# Fubarino_SD_v14.net
KiCad netlist of a schematic drawn in EAGLE
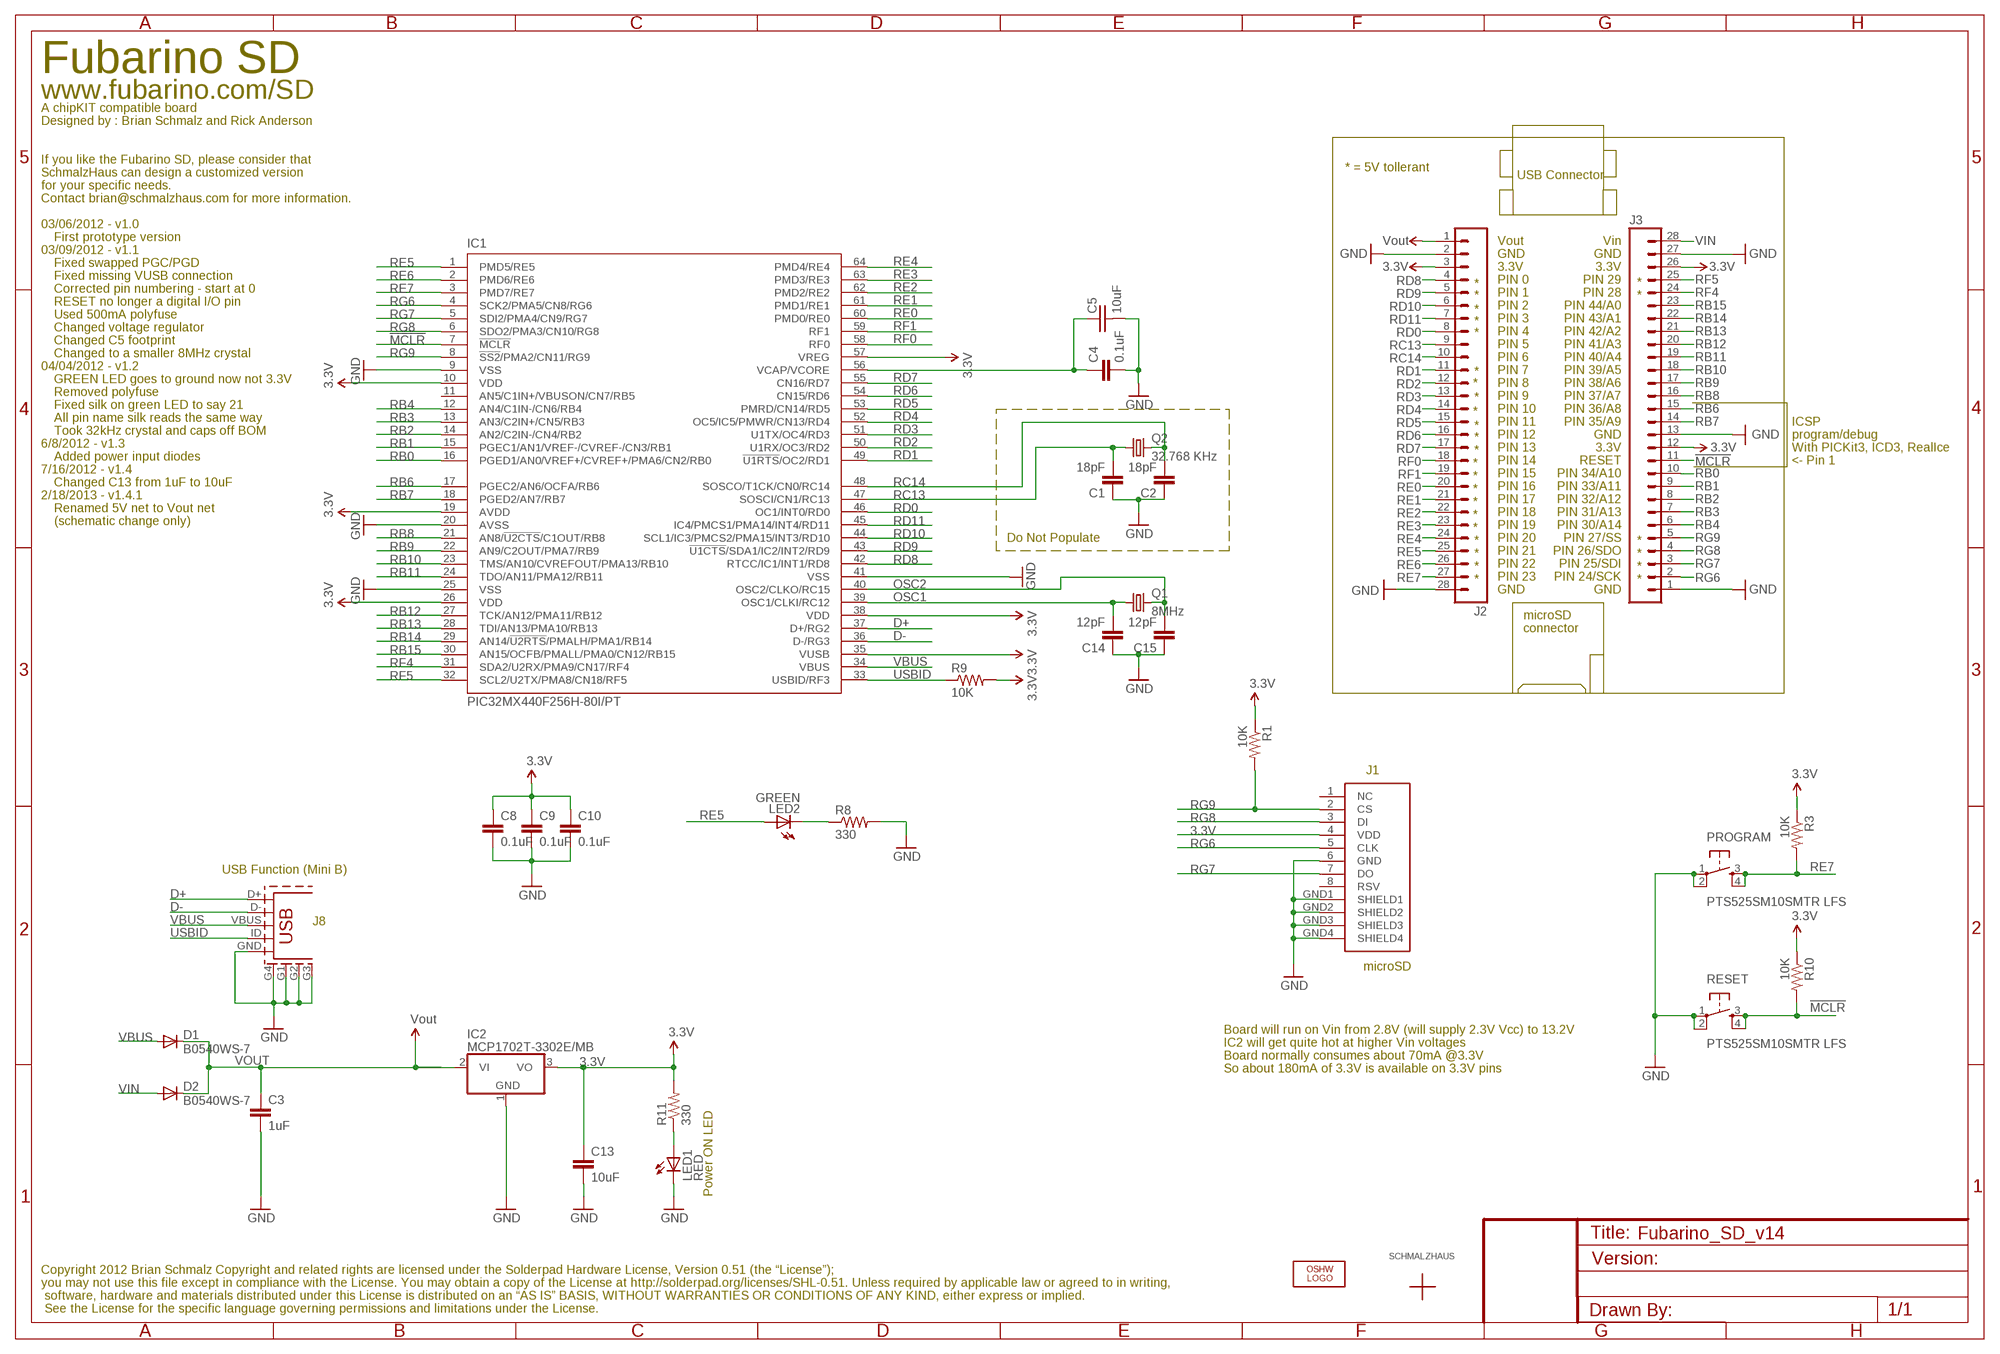
[diagram p0: schematic, sheet 1]

(export (version "E")
  (design (tool "Eeschema 10.0.6"))
  (components
    (comp (ref "C1")
      (value "18pF")
      (footprint "eagle-import:0603-CAP")
      (libsource (lib "eagle-import") (part "CAP0603-CAP"))
    )
    (comp (ref "C2")
      (value "18pF")
      (footprint "eagle-import:0603-CAP")
      (libsource (lib "eagle-import") (part "CAP0603-CAP"))
    )
    (comp (ref "C3")
      (value "1uF")
      (footprint "eagle-import:0603-CAP")
      (libsource (lib "eagle-import") (part "CAP0603-CAP"))
    )
    (comp (ref "C4")
      (value "0.1uF")
      (footprint "eagle-import:0603-CAP")
      (libsource (lib "eagle-import") (part "CAP0603-CAP"))
    )
    (comp (ref "C5")
      (value "10uF")
      (footprint "eagle-import:CAP_0805")
      (libsource (lib "eagle-import") (part "CAP0805"))
    )
    (comp (ref "C8")
      (value "0.1uF")
      (footprint "eagle-import:0603-CAP")
      (libsource (lib "eagle-import") (part "CAP0603-CAP"))
    )
    (comp (ref "C9")
      (value "0.1uF")
      (footprint "eagle-import:0603-CAP")
      (libsource (lib "eagle-import") (part "CAP0603-CAP"))
    )
    (comp (ref "C10")
      (value "0.1uF")
      (footprint "eagle-import:0603")
      (libsource (lib "eagle-import") (part "CAP0603"))
    )
    (comp (ref "C13")
      (value "10uF")
      (footprint "eagle-import:0805")
      (libsource (lib "eagle-import") (part "SparkFun02-20-08_CAP0805"))
    )
    (comp (ref "C14")
      (value "12pF")
      (footprint "eagle-import:0603-CAP")
      (libsource (lib "eagle-import") (part "CAP0603-CAP"))
    )
    (comp (ref "C15")
      (value "12pF")
      (footprint "eagle-import:0603-CAP")
      (libsource (lib "eagle-import") (part "CAP0603-CAP"))
    )
    (comp (ref "D1")
      (value "B0540WS-7")
      (footprint "eagle-import:SOD-323")
      (libsource (lib "eagle-import") (part "DIODESOD"))
    )
    (comp (ref "D2")
      (value "B0540WS-7")
      (footprint "eagle-import:SOD-323")
      (libsource (lib "eagle-import") (part "DIODESOD"))
    )
    (comp (ref "IC1")
      (value "PIC32MX440F256H-80I/PT")
      (footprint "eagle-import:TQFP64-10X10")
      (libsource (lib "eagle-import") (part "PIC32MX440F256H"))
    )
    (comp (ref "IC2")
      (value "MCP1702T-3302E/MB")
      (footprint "eagle-import:SOT89")
      (libsource (lib "eagle-import") (part "MCP1703MB33"))
    )
    (comp (ref "J1")
      (value "MICRO_SD_CARD_SOCKET")
      (footprint "eagle-import:SD-MMC_SOCKET-PP")
      (libsource (lib "eagle-import") (part "MICRO_SD_CARD_SOCKET"))
    )
    (comp (ref "J2")
      (value "M28USEPIN1")
      (footprint "eagle-import:1X28")
      (libsource (lib "eagle-import") (part "M28USEPIN1"))
    )
    (comp (ref "J3")
      (value "M28NOPIN1")
      (footprint "eagle-import:1X28_NO_PIN_1")
      (libsource (lib "eagle-import") (part "M28NOPIN1"))
    )
    (comp (ref "J8")
      (value "UX60A-MB-5ST")
      (footprint "eagle-import:USB-MINIB")
      (libsource (lib "eagle-import") (part "USB_5PIN"))
    )
    (comp (ref "LED1")
      (value "RED")
      (footprint "eagle-import:LED-0603")
      (libsource (lib "eagle-import") (part "LED0603"))
    )
    (comp (ref "LED2")
      (value "GREEN")
      (footprint "eagle-import:LED-0603")
      (libsource (lib "eagle-import") (part "LED0603"))
    )
    (comp (ref "LOGO1")
      (value "OSHW_LOGO_8MILX0070-NT")
      (footprint "eagle-import:OSHW_8X70_NOTEXT")
      (libsource (lib "eagle-import") (part "OSHW_LOGO_8MILX0070-NT"))
    )
    (comp (ref "PROGRAM")
      (value "PTS525SM10SMTR LFS")
      (footprint "eagle-import:TACTILE_SWITCH_SMD")
      (libsource (lib "eagle-import") (part "TAC_SWITCHSND"))
    )
    (comp (ref "Q1")
      (value "8MHz")
      (footprint "eagle-import:NX5032_5MM_3.2MM_CRYSTAL")
      (libsource (lib "eagle-import") (part "CRYSTALNX5032"))
    )
    (comp (ref "Q2")
      (value "32.768 KHz")
      (footprint "eagle-import:TC26H")
      (libsource (lib "eagle-import") (part "CRYSTALTC26H"))
    )
    (comp (ref "R1")
      (value "10K")
      (footprint "eagle-import:0603-RES")
      (libsource (lib "eagle-import") (part "RESISTOR0603-RES"))
    )
    (comp (ref "R3")
      (value "10K")
      (footprint "eagle-import:0603-RES")
      (libsource (lib "eagle-import") (part "RESISTOR0603-RES"))
    )
    (comp (ref "R8")
      (value "330")
      (footprint "eagle-import:0603-RES")
      (libsource (lib "eagle-import") (part "RESISTOR0603-RES"))
    )
    (comp (ref "R9")
      (value "10K")
      (footprint "eagle-import:0603-RES")
      (libsource (lib "eagle-import") (part "RESISTOR0603-RES"))
    )
    (comp (ref "R10")
      (value "10K")
      (footprint "eagle-import:0603-RES")
      (libsource (lib "eagle-import") (part "RESISTOR0603-RES"))
    )
    (comp (ref "R11")
      (value "330")
      (footprint "eagle-import:0603-RES")
      (libsource (lib "eagle-import") (part "RESISTOR0603-RES"))
    )
    (comp (ref "RESET")
      (value "PTS525SM10SMTR LFS")
      (footprint "eagle-import:TACTILE_SWITCH_SMD")
      (libsource (lib "eagle-import") (part "TAC_SWITCHSND"))
    )
    (comp (ref "U$1")
      (value "SCHMALZHAUSSCHMALZHAUS_SMALL")
      (footprint "eagle-import:SCHMALZHAUS_SMALL")
      (libsource (lib "eagle-import") (part "SCHMALZHAUSSCHMALZHAUS_SMALL"))
    )
  )
  (nets
    (net (code "1") (name "/D+") (class "Default")
      (node (ref "IC1") (pin "37") (pinfunction "D+/RG2_37") (pintype "bidirectional"))
      (node (ref "J8") (pin "D+") (pinfunction "D+_D+") (pintype "bidirectional"))
    )
    (net (code "2") (name "/D-") (class "Default")
      (node (ref "IC1") (pin "36") (pinfunction "D-/RG3_36") (pintype "bidirectional"))
      (node (ref "J8") (pin "D-") (pinfunction "D-_D-") (pintype "bidirectional"))
    )
    (net (code "3") (name "/OSC1") (class "Default")
      (node (ref "C14") (pin "2") (pinfunction "2_2") (pintype "passive"))
      (node (ref "IC1") (pin "39") (pinfunction "OSC1/CLKI/RC12_39") (pintype "bidirectional"))
      (node (ref "Q1") (pin "1") (pinfunction "1_1") (pintype "passive"))
    )
    (net (code "4") (name "/OSC2") (class "Default")
      (node (ref "C15") (pin "2") (pinfunction "2_2") (pintype "passive"))
      (node (ref "IC1") (pin "40") (pinfunction "OSC2/CLKO/RC15_40") (pintype "bidirectional"))
      (node (ref "Q1") (pin "2") (pinfunction "2_2") (pintype "passive"))
    )
    (net (code "5") (name "/RB0") (class "Default")
      (node (ref "IC1") (pin "16") (pinfunction "PGED1/AN0/VREF+/CVREF+/PMA6/CN2/RB0_16") (pintype "bidirectional"))
      (node (ref "J3") (pin "10") (pinfunction "10_10") (pintype "passive"))
    )
    (net (code "6") (name "/RB1") (class "Default")
      (node (ref "IC1") (pin "15") (pinfunction "PGEC1/AN1/VREF-/CVREF-/CN3/RB1_15") (pintype "bidirectional"))
      (node (ref "J3") (pin "9") (pinfunction "9_9") (pintype "passive"))
    )
    (net (code "7") (name "/RB2") (class "Default")
      (node (ref "IC1") (pin "14") (pinfunction "AN2/C2IN-/CN4/RB2_14") (pintype "bidirectional"))
      (node (ref "J3") (pin "8") (pinfunction "8_8") (pintype "passive"))
    )
    (net (code "8") (name "/RB3") (class "Default")
      (node (ref "IC1") (pin "13") (pinfunction "AN3/C2IN+/CN5/RB3_13") (pintype "bidirectional"))
      (node (ref "J3") (pin "7") (pinfunction "7_7") (pintype "passive"))
    )
    (net (code "9") (name "/RB4") (class "Default")
      (node (ref "IC1") (pin "12") (pinfunction "AN4/C1IN-/CN6/RB4_12") (pintype "bidirectional"))
      (node (ref "J3") (pin "6") (pinfunction "6_6") (pintype "passive"))
    )
    (net (code "10") (name "/RB6") (class "Default")
      (node (ref "IC1") (pin "17") (pinfunction "PGEC2/AN6/OCFA/RB6_17") (pintype "bidirectional"))
      (node (ref "J3") (pin "15") (pinfunction "15_15") (pintype "passive"))
    )
    (net (code "11") (name "/RB7") (class "Default")
      (node (ref "IC1") (pin "18") (pinfunction "PGED2/AN7/RB7_18") (pintype "bidirectional"))
      (node (ref "J3") (pin "14") (pinfunction "14_14") (pintype "passive"))
    )
    (net (code "12") (name "/RB8") (class "Default")
      (node (ref "IC1") (pin "21") (pinfunction "AN8/~{U2CTS}/C1OUT/RB8_21") (pintype "bidirectional"))
      (node (ref "J3") (pin "16") (pinfunction "16_16") (pintype "passive"))
    )
    (net (code "13") (name "/RB9") (class "Default")
      (node (ref "IC1") (pin "22") (pinfunction "AN9/C2OUT/PMA7/RB9_22") (pintype "bidirectional"))
      (node (ref "J3") (pin "17") (pinfunction "17_17") (pintype "passive"))
    )
    (net (code "14") (name "/RB10") (class "Default")
      (node (ref "IC1") (pin "23") (pinfunction "TMS/AN10/CVREFOUT/PMA13/RB10_23") (pintype "input"))
      (node (ref "J3") (pin "18") (pinfunction "18_18") (pintype "passive"))
    )
    (net (code "15") (name "/RB11") (class "Default")
      (node (ref "IC1") (pin "24") (pinfunction "TDO/AN11/PMA12/RB11_24") (pintype "output"))
      (node (ref "J3") (pin "19") (pinfunction "19_19") (pintype "passive"))
    )
    (net (code "16") (name "/RB12") (class "Default")
      (node (ref "IC1") (pin "27") (pinfunction "TCK/AN12/PMA11/RB12_27") (pintype "input"))
      (node (ref "J3") (pin "20") (pinfunction "20_20") (pintype "passive"))
    )
    (net (code "17") (name "/RB13") (class "Default")
      (node (ref "IC1") (pin "28") (pinfunction "TDI/AN13/PMA10/RB13_28") (pintype "input"))
      (node (ref "J3") (pin "21") (pinfunction "21_21") (pintype "passive"))
    )
    (net (code "18") (name "/RB14") (class "Default")
      (node (ref "IC1") (pin "29") (pinfunction "AN14/~{U2RTS}/PMALH/PMA1/RB14_29") (pintype "bidirectional"))
      (node (ref "J3") (pin "22") (pinfunction "22_22") (pintype "passive"))
    )
    (net (code "19") (name "/RB15") (class "Default")
      (node (ref "IC1") (pin "30") (pinfunction "AN15/OCFB/PMALL/PMA0/CN12/RB15_30") (pintype "bidirectional"))
      (node (ref "J3") (pin "23") (pinfunction "23_23") (pintype "passive"))
    )
    (net (code "20") (name "/RC13") (class "Default")
      (node (ref "C1") (pin "2") (pinfunction "2_2") (pintype "passive"))
      (node (ref "IC1") (pin "47") (pinfunction "SOSCI/CN1/RC13_47") (pintype "bidirectional"))
      (node (ref "J2") (pin "9") (pinfunction "9_9") (pintype "passive"))
      (node (ref "Q2") (pin "1") (pinfunction "1_1") (pintype "passive"))
    )
    (net (code "21") (name "/RC14") (class "Default")
      (node (ref "C2") (pin "2") (pinfunction "2_2") (pintype "passive"))
      (node (ref "IC1") (pin "48") (pinfunction "SOSCO/T1CK/CN0/RC14_48") (pintype "bidirectional"))
      (node (ref "J2") (pin "10") (pinfunction "10_10") (pintype "passive"))
      (node (ref "Q2") (pin "2") (pinfunction "2_2") (pintype "passive"))
    )
    (net (code "22") (name "/RD0") (class "Default")
      (node (ref "IC1") (pin "46") (pinfunction "OC1/INT0/RD0_46") (pintype "bidirectional"))
      (node (ref "J2") (pin "8") (pinfunction "8_8") (pintype "passive"))
    )
    (net (code "23") (name "/RD1") (class "Default")
      (node (ref "IC1") (pin "49") (pinfunction "~{U1RTS}/OC2/RD1_49") (pintype "bidirectional"))
      (node (ref "J2") (pin "11") (pinfunction "11_11") (pintype "passive"))
    )
    (net (code "24") (name "/RD2") (class "Default")
      (node (ref "IC1") (pin "50") (pinfunction "U1RX/OC3/RD2_50") (pintype "bidirectional"))
      (node (ref "J2") (pin "12") (pinfunction "12_12") (pintype "passive"))
    )
    (net (code "25") (name "/RD3") (class "Default")
      (node (ref "IC1") (pin "51") (pinfunction "U1TX/OC4/RD3_51") (pintype "bidirectional"))
      (node (ref "J2") (pin "13") (pinfunction "13_13") (pintype "passive"))
    )
    (net (code "26") (name "/RD4") (class "Default")
      (node (ref "IC1") (pin "52") (pinfunction "OC5/IC5/PMWR/CN13/RD4_52") (pintype "bidirectional"))
      (node (ref "J2") (pin "14") (pinfunction "14_14") (pintype "passive"))
    )
    (net (code "27") (name "/RD5") (class "Default")
      (node (ref "IC1") (pin "53") (pinfunction "PMRD/CN14/RD5_53") (pintype "bidirectional"))
      (node (ref "J2") (pin "15") (pinfunction "15_15") (pintype "passive"))
    )
    (net (code "28") (name "/RD6") (class "Default")
      (node (ref "IC1") (pin "54") (pinfunction "CN15/RD6_54") (pintype "bidirectional"))
      (node (ref "J2") (pin "16") (pinfunction "16_16") (pintype "passive"))
    )
    (net (code "29") (name "/RD7") (class "Default")
      (node (ref "IC1") (pin "55") (pinfunction "CN16/RD7_55") (pintype "bidirectional"))
      (node (ref "J2") (pin "17") (pinfunction "17_17") (pintype "passive"))
    )
    (net (code "30") (name "/RD8") (class "Default")
      (node (ref "IC1") (pin "42") (pinfunction "RTCC/IC1/INT1/RD8_42") (pintype "bidirectional"))
      (node (ref "J2") (pin "4") (pinfunction "4_4") (pintype "passive"))
    )
    (net (code "31") (name "/RD9") (class "Default")
      (node (ref "IC1") (pin "43") (pinfunction "~{U1CTS}/SDA1/IC2/INT2/RD9_43") (pintype "bidirectional"))
      (node (ref "J2") (pin "5") (pinfunction "5_5") (pintype "passive"))
    )
    (net (code "32") (name "/RD10") (class "Default")
      (node (ref "IC1") (pin "44") (pinfunction "SCL1/IC3/PMCS2/PMA15/INT3/RD10_44") (pintype "bidirectional"))
      (node (ref "J2") (pin "6") (pinfunction "6_6") (pintype "passive"))
    )
    (net (code "33") (name "/RD11") (class "Default")
      (node (ref "IC1") (pin "45") (pinfunction "IC4/PMCS1/PMA14/INT4/RD11_45") (pintype "bidirectional"))
      (node (ref "J2") (pin "7") (pinfunction "7_7") (pintype "passive"))
    )
    (net (code "34") (name "/RE0") (class "Default")
      (node (ref "IC1") (pin "60") (pinfunction "PMD0/RE0_60") (pintype "bidirectional"))
      (node (ref "J2") (pin "20") (pinfunction "20_20") (pintype "passive"))
    )
    (net (code "35") (name "/RE1") (class "Default")
      (node (ref "IC1") (pin "61") (pinfunction "PMD1/RE1_61") (pintype "bidirectional"))
      (node (ref "J2") (pin "21") (pinfunction "21_21") (pintype "passive"))
    )
    (net (code "36") (name "/RE2") (class "Default")
      (node (ref "IC1") (pin "62") (pinfunction "PMD2/RE2_62") (pintype "bidirectional"))
      (node (ref "J2") (pin "22") (pinfunction "22_22") (pintype "passive"))
    )
    (net (code "37") (name "/RE3") (class "Default")
      (node (ref "IC1") (pin "63") (pinfunction "PMD3/RE3_63") (pintype "bidirectional"))
      (node (ref "J2") (pin "23") (pinfunction "23_23") (pintype "passive"))
    )
    (net (code "38") (name "/RE4") (class "Default")
      (node (ref "IC1") (pin "64") (pinfunction "PMD4/RE4_64") (pintype "bidirectional"))
      (node (ref "J2") (pin "24") (pinfunction "24_24") (pintype "passive"))
    )
    (net (code "39") (name "/RE5") (class "Default")
      (node (ref "IC1") (pin "1") (pinfunction "PMD5/RE5_1") (pintype "bidirectional"))
      (node (ref "J2") (pin "25") (pinfunction "25_25") (pintype "passive"))
      (node (ref "LED2") (pin "A") (pinfunction "A_A") (pintype "passive"))
    )
    (net (code "40") (name "/RE6") (class "Default")
      (node (ref "IC1") (pin "2") (pinfunction "PMD6/RE6_2") (pintype "bidirectional"))
      (node (ref "J2") (pin "26") (pinfunction "26_26") (pintype "passive"))
    )
    (net (code "41") (name "/RE7") (class "Default")
      (node (ref "IC1") (pin "3") (pinfunction "PMD7/RE7_3") (pintype "bidirectional"))
      (node (ref "J2") (pin "27") (pinfunction "27_27") (pintype "passive"))
      (node (ref "PROGRAM") (pin "3") (pinfunction "3_3") (pintype "passive"))
      (node (ref "PROGRAM") (pin "4") (pinfunction "4_4") (pintype "passive"))
      (node (ref "R3") (pin "2") (pinfunction "2_2") (pintype "passive"))
    )
    (net (code "42") (name "/RF0") (class "Default")
      (node (ref "IC1") (pin "58") (pinfunction "RF0_58") (pintype "bidirectional"))
      (node (ref "J2") (pin "18") (pinfunction "18_18") (pintype "passive"))
    )
    (net (code "43") (name "/RF1") (class "Default")
      (node (ref "IC1") (pin "59") (pinfunction "RF1_59") (pintype "bidirectional"))
      (node (ref "J2") (pin "19") (pinfunction "19_19") (pintype "passive"))
    )
    (net (code "44") (name "/RF4") (class "Default")
      (node (ref "IC1") (pin "31") (pinfunction "SDA2/U2RX/PMA9/CN17/RF4_31") (pintype "bidirectional"))
      (node (ref "J3") (pin "24") (pinfunction "24_24") (pintype "passive"))
    )
    (net (code "45") (name "/RF5") (class "Default")
      (node (ref "IC1") (pin "32") (pinfunction "SCL2/U2TX/PMA8/CN18/RF5_32") (pintype "bidirectional"))
      (node (ref "J3") (pin "25") (pinfunction "25_25") (pintype "passive"))
    )
    (net (code "46") (name "/RG6") (class "Default")
      (node (ref "IC1") (pin "4") (pinfunction "SCK2/PMA5/CN8/RG6_4") (pintype "bidirectional"))
      (node (ref "J1") (pin "5") (pinfunction "CLK_5") (pintype "bidirectional"))
      (node (ref "J3") (pin "2") (pinfunction "2_2") (pintype "passive"))
    )
    (net (code "47") (name "/RG7") (class "Default")
      (node (ref "IC1") (pin "5") (pinfunction "SDI2/PMA4/CN9/RG7_5") (pintype "bidirectional"))
      (node (ref "J1") (pin "7") (pinfunction "DO_7") (pintype "bidirectional"))
      (node (ref "J3") (pin "3") (pinfunction "3_3") (pintype "passive"))
    )
    (net (code "48") (name "/RG8") (class "Default")
      (node (ref "IC1") (pin "6") (pinfunction "SDO2/PMA3/CN10/RG8_6") (pintype "bidirectional"))
      (node (ref "J1") (pin "3") (pinfunction "DI_3") (pintype "bidirectional"))
      (node (ref "J3") (pin "4") (pinfunction "4_4") (pintype "passive"))
    )
    (net (code "49") (name "/RG9") (class "Default")
      (node (ref "IC1") (pin "8") (pinfunction "~{SS2}/PMA2/CN11/RG9_8") (pintype "bidirectional"))
      (node (ref "J1") (pin "2") (pinfunction "CS_2") (pintype "bidirectional"))
      (node (ref "J3") (pin "5") (pinfunction "5_5") (pintype "passive"))
      (node (ref "R1") (pin "2") (pinfunction "2_2") (pintype "passive"))
    )
    (net (code "50") (name "/USBID") (class "Default")
      (node (ref "IC1") (pin "33") (pinfunction "USBID/RF3_33") (pintype "bidirectional"))
      (node (ref "J8") (pin "ID") (pinfunction "USB_ID_ID") (pintype "bidirectional"))
      (node (ref "R9") (pin "1") (pinfunction "1_1") (pintype "passive"))
    )
    (net (code "51") (name "/VBUS") (class "Default")
      (node (ref "D1") (pin "2") (pinfunction "A_2") (pintype "passive"))
      (node (ref "IC1") (pin "34") (pinfunction "VBUS_34") (pintype "bidirectional"))
      (node (ref "J8") (pin "VBUS") (pinfunction "VBUS_VBUS") (pintype "bidirectional"))
    )
    (net (code "52") (name "/VIN") (class "Default")
      (node (ref "D2") (pin "2") (pinfunction "A_2") (pintype "passive"))
      (node (ref "J3") (pin "28") (pinfunction "28_28") (pintype "passive"))
    )
    (net (code "53") (name "/~{MCLR}") (class "Default")
      (node (ref "IC1") (pin "7") (pinfunction "~{MCLR}_7") (pintype "input"))
      (node (ref "J3") (pin "11") (pinfunction "11_11") (pintype "passive"))
      (node (ref "R10") (pin "2") (pinfunction "2_2") (pintype "passive"))
      (node (ref "RESET") (pin "3") (pinfunction "3_3") (pintype "passive"))
      (node (ref "RESET") (pin "4") (pinfunction "4_4") (pintype "passive"))
    )
    (net (code "54") (name "3.3V") (class "Default")
      (node (ref "C10") (pin "1") (pinfunction "1_1") (pintype "passive"))
      (node (ref "C13") (pin "1") (pinfunction "1_1") (pintype "passive"))
      (node (ref "C8") (pin "1") (pinfunction "1_1") (pintype "passive"))
      (node (ref "C9") (pin "1") (pinfunction "1_1") (pintype "passive"))
      (node (ref "IC1") (pin "10") (pinfunction "VDD_10") (pintype "power_in"))
      (node (ref "IC1") (pin "19") (pinfunction "AVDD_19") (pintype "power_in"))
      (node (ref "IC1") (pin "26") (pinfunction "VDD_26") (pintype "power_in"))
      (node (ref "IC1") (pin "35") (pinfunction "VUSB_35") (pintype "passive"))
      (node (ref "IC1") (pin "38") (pinfunction "VDD_38") (pintype "power_in"))
      (node (ref "IC1") (pin "57") (pinfunction "VREG_57") (pintype "passive"))
      (node (ref "IC2") (pin "3") (pinfunction "VO_3") (pintype "passive"))
      (node (ref "J1") (pin "4") (pinfunction "VDD_4") (pintype "bidirectional"))
      (node (ref "J2") (pin "3") (pinfunction "3_3") (pintype "passive"))
      (node (ref "J3") (pin "12") (pinfunction "12_12") (pintype "passive"))
      (node (ref "J3") (pin "26") (pinfunction "26_26") (pintype "passive"))
      (node (ref "R1") (pin "1") (pinfunction "1_1") (pintype "passive"))
      (node (ref "R10") (pin "1") (pinfunction "1_1") (pintype "passive"))
      (node (ref "R11") (pin "2") (pinfunction "2_2") (pintype "passive"))
      (node (ref "R3") (pin "1") (pinfunction "1_1") (pintype "passive"))
      (node (ref "R9") (pin "2") (pinfunction "2_2") (pintype "passive"))
    )
    (net (code "55") (name "GND") (class "Default")
      (node (ref "C1") (pin "1") (pinfunction "1_1") (pintype "passive"))
      (node (ref "C10") (pin "2") (pinfunction "2_2") (pintype "passive"))
      (node (ref "C13") (pin "2") (pinfunction "2_2") (pintype "passive"))
      (node (ref "C14") (pin "1") (pinfunction "1_1") (pintype "passive"))
      (node (ref "C15") (pin "1") (pinfunction "1_1") (pintype "passive"))
      (node (ref "C2") (pin "1") (pinfunction "1_1") (pintype "passive"))
      (node (ref "C3") (pin "2") (pinfunction "2_2") (pintype "passive"))
      (node (ref "C4") (pin "2") (pinfunction "2_2") (pintype "passive"))
      (node (ref "C5") (pin "2") (pinfunction "2_2") (pintype "passive"))
      (node (ref "C8") (pin "2") (pinfunction "2_2") (pintype "passive"))
      (node (ref "C9") (pin "2") (pinfunction "2_2") (pintype "passive"))
      (node (ref "IC1") (pin "20") (pinfunction "AVSS_20") (pintype "power_in"))
      (node (ref "IC1") (pin "25") (pinfunction "VSS_25") (pintype "power_in"))
      (node (ref "IC1") (pin "41") (pinfunction "VSS_41") (pintype "power_in"))
      (node (ref "IC1") (pin "9") (pinfunction "VSS_9") (pintype "power_in"))
      (node (ref "IC2") (pin "1") (pinfunction "GND_1") (pintype "passive"))
      (node (ref "J1") (pin "6") (pinfunction "GND_6") (pintype "bidirectional"))
      (node (ref "J1") (pin "GND1") (pinfunction "SHIELD1_GND1") (pintype "bidirectional"))
      (node (ref "J1") (pin "GND2") (pinfunction "SHIELD2_GND2") (pintype "bidirectional"))
      (node (ref "J1") (pin "GND3") (pinfunction "SHIELD3_GND3") (pintype "bidirectional"))
      (node (ref "J1") (pin "GND4") (pinfunction "SHIELD4_GND4") (pintype "bidirectional"))
      (node (ref "J2") (pin "2") (pinfunction "2_2") (pintype "passive"))
      (node (ref "J2") (pin "28") (pinfunction "28_28") (pintype "passive"))
      (node (ref "J3") (pin "1") (pinfunction "1_1") (pintype "passive"))
      (node (ref "J3") (pin "13") (pinfunction "13_13") (pintype "passive"))
      (node (ref "J3") (pin "27") (pinfunction "27_27") (pintype "passive"))
      (node (ref "J8") (pin "G1") (pinfunction "P$1_G1") (pintype "bidirectional"))
      (node (ref "J8") (pin "G2") (pinfunction "P$2_G2") (pintype "bidirectional"))
      (node (ref "J8") (pin "G3") (pinfunction "P$3_G3") (pintype "bidirectional"))
      (node (ref "J8") (pin "G4") (pinfunction "SHIELD_G4") (pintype "bidirectional"))
      (node (ref "J8") (pin "GND") (pinfunction "GND_GND") (pintype "bidirectional"))
      (node (ref "LED1") (pin "C") (pinfunction "C_C") (pintype "passive"))
      (node (ref "PROGRAM") (pin "1") (pinfunction "1_1") (pintype "passive"))
      (node (ref "PROGRAM") (pin "2") (pinfunction "2_2") (pintype "passive"))
      (node (ref "R8") (pin "2") (pinfunction "2_2") (pintype "passive"))
      (node (ref "RESET") (pin "1") (pinfunction "1_1") (pintype "passive"))
      (node (ref "RESET") (pin "2") (pinfunction "2_2") (pintype "passive"))
    )
    (net (code "56") (name "Net-(IC1-VCAP{slash}VCORE)") (class "Default")
      (node (ref "C4") (pin "1") (pinfunction "1_1") (pintype "passive"))
      (node (ref "C5") (pin "1") (pinfunction "1_1") (pintype "passive"))
      (node (ref "IC1") (pin "56") (pinfunction "VCAP/VCORE_56") (pintype "power_in"))
    )
    (net (code "57") (name "Net-(LED1-PadA)") (class "Default")
      (node (ref "LED1") (pin "A") (pinfunction "A_A") (pintype "passive"))
      (node (ref "R11") (pin "1") (pinfunction "1_1") (pintype "passive"))
    )
    (net (code "58") (name "Net-(LED2-PadC)") (class "Default")
      (node (ref "LED2") (pin "C") (pinfunction "C_C") (pintype "passive"))
      (node (ref "R8") (pin "1") (pinfunction "1_1") (pintype "passive"))
    )
    (net (code "59") (name "Vout") (class "Default")
      (node (ref "C3") (pin "1") (pinfunction "1_1") (pintype "passive"))
      (node (ref "D1") (pin "1") (pinfunction "C_1") (pintype "passive"))
      (node (ref "D2") (pin "1") (pinfunction "C_1") (pintype "passive"))
      (node (ref "IC2") (pin "2") (pinfunction "VI_2") (pintype "input"))
      (node (ref "IC2") (pin "2@1") (pinfunction "VI1_2@1") (pintype "input"))
      (node (ref "J2") (pin "1") (pinfunction "1_1") (pintype "passive"))
    )
    (net (code "60") (name "unconnected-(IC1-AN5{slash}C1IN+{slash}VBUSON{slash}CN7{slash}RB5-Pad11)") (class "Default")
      (node (ref "IC1") (pin "11") (pinfunction "AN5/C1IN+/VBUSON/CN7/RB5_11") (pintype "bidirectional"))
    )
    (net (code "61") (name "unconnected-(J1-NC-Pad1)") (class "Default")
      (node (ref "J1") (pin "1") (pinfunction "NC_1") (pintype "bidirectional"))
    )
    (net (code "62") (name "unconnected-(J1-RSV-Pad8)") (class "Default")
      (node (ref "J1") (pin "8") (pinfunction "RSV_8") (pintype "bidirectional"))
    )
  )
)
